# main.net
KiCad netlist of a schematic drawn in Altium Designer
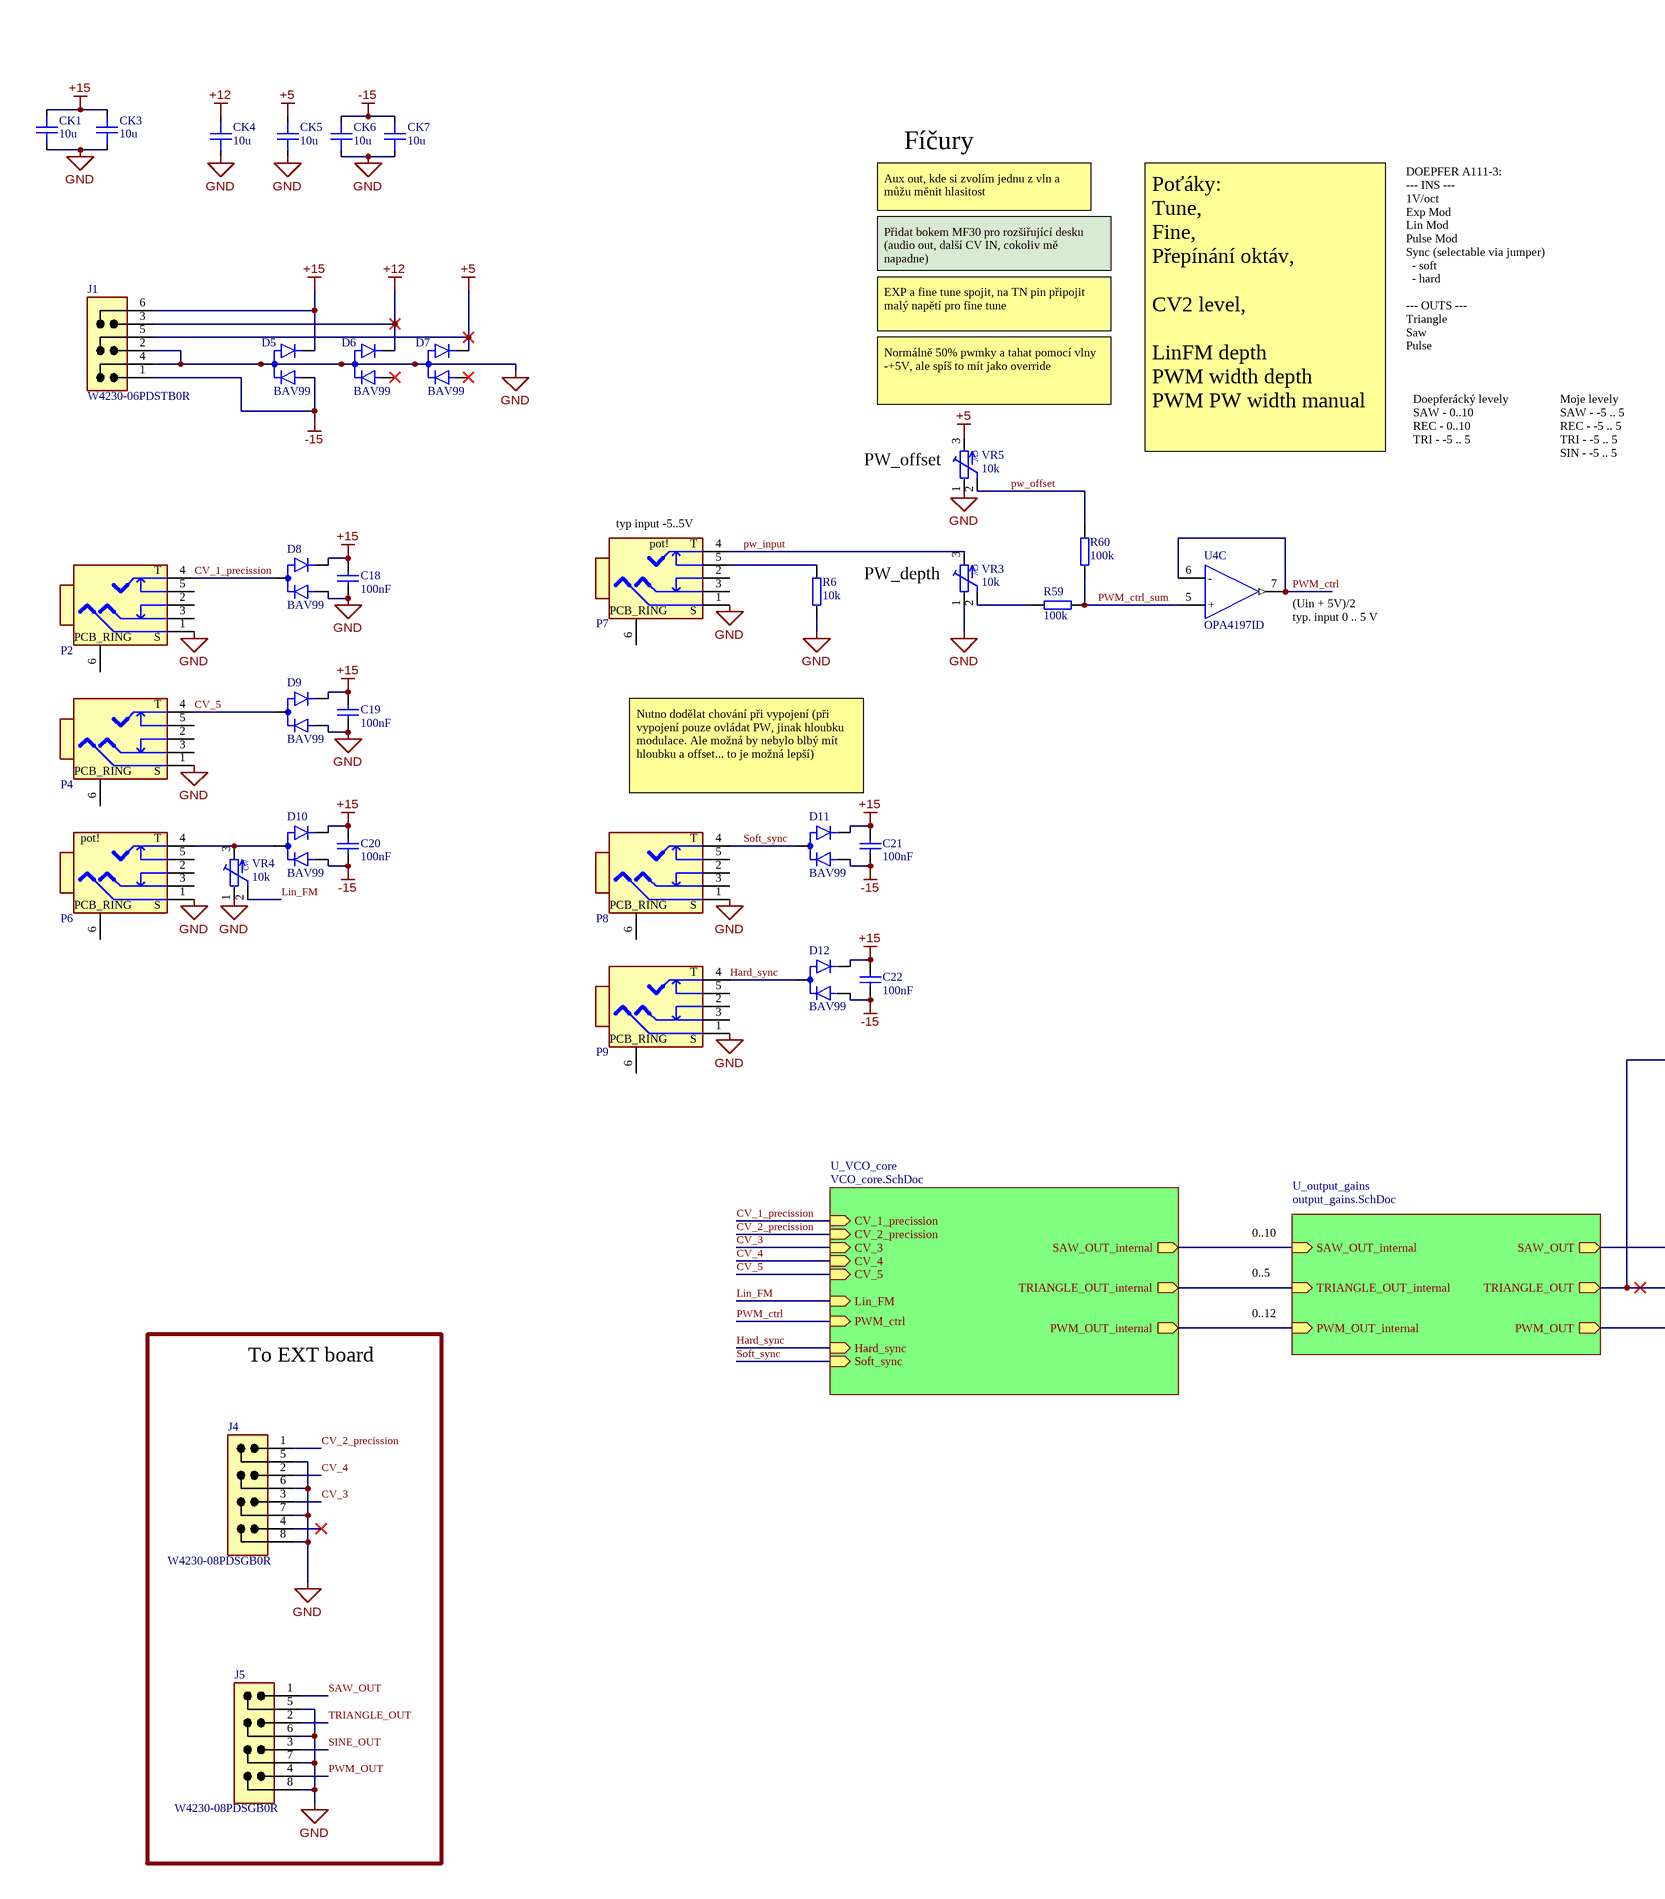
[diagram p0: main.SchDoc, left]
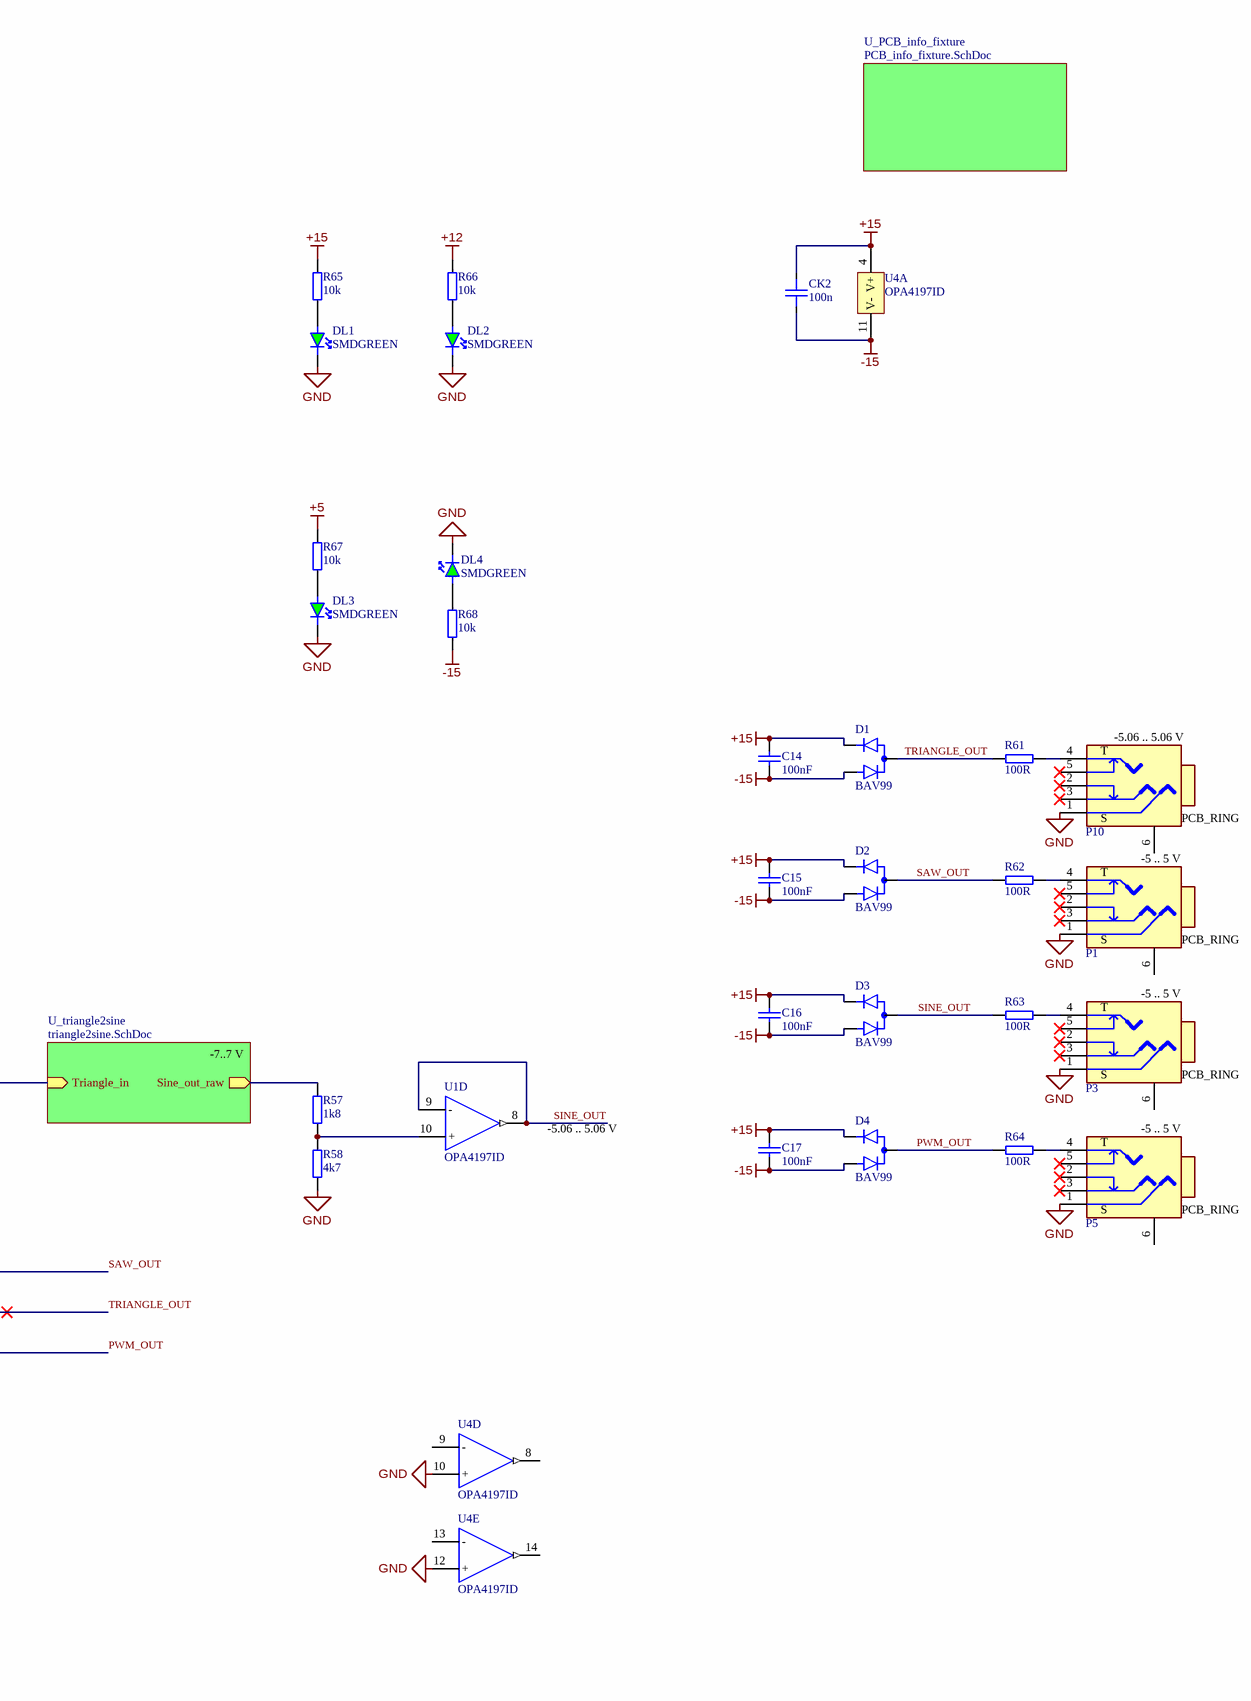
[diagram p1: main.SchDoc, right]

(export (version "E")
  (design (tool "Eeschema 10.0.6"))
  (components
    (comp (ref "C14")
      (value "100nF")
      (footprint "WCAP-CSGP_0603_L1.6W0.8H0.8_Reflow")
      (description "WCAP-CSGP Multilayer Ceramic Chip Capacitor, General Purpose, size 0603, X7R, 100nF, 50V")
      (fields
        (field (name "MANUFACTURER") "Wurth Elektronik")
        (field (name "MANUFACTURER PART NUMBER") "885012206095")
      )
      (libsource (lib "Altium_WCAP-CSGP (rev22a)") (part "885012206095"))
    )
    (comp (ref "C15")
      (value "100nF")
      (footprint "WCAP-CSGP_0603_L1.6W0.8H0.8_Reflow")
      (description "WCAP-CSGP Multilayer Ceramic Chip Capacitor, General Purpose, size 0603, X7R, 100nF, 50V")
      (fields
        (field (name "MANUFACTURER") "Wurth Elektronik")
        (field (name "MANUFACTURER PART NUMBER") "885012206095")
      )
      (libsource (lib "Altium_WCAP-CSGP (rev22a)") (part "885012206095"))
    )
    (comp (ref "C16")
      (value "100nF")
      (footprint "WCAP-CSGP_0603_L1.6W0.8H0.8_Reflow")
      (description "WCAP-CSGP Multilayer Ceramic Chip Capacitor, General Purpose, size 0603, X7R, 100nF, 50V")
      (fields
        (field (name "MANUFACTURER") "Wurth Elektronik")
        (field (name "MANUFACTURER PART NUMBER") "885012206095")
      )
      (libsource (lib "Altium_WCAP-CSGP (rev22a)") (part "885012206095"))
    )
    (comp (ref "C17")
      (value "100nF")
      (footprint "WCAP-CSGP_0603_L1.6W0.8H0.8_Reflow")
      (description "WCAP-CSGP Multilayer Ceramic Chip Capacitor, General Purpose, size 0603, X7R, 100nF, 50V")
      (fields
        (field (name "MANUFACTURER") "Wurth Elektronik")
        (field (name "MANUFACTURER PART NUMBER") "885012206095")
      )
      (libsource (lib "Altium_WCAP-CSGP (rev22a)") (part "885012206095"))
    )
    (comp (ref "C18")
      (value "100nF")
      (footprint "WCAP-CSGP_0603_L1.6W0.8H0.8_Reflow")
      (description "WCAP-CSGP Multilayer Ceramic Chip Capacitor, General Purpose, size 0603, X7R, 100nF, 50V")
      (fields
        (field (name "MANUFACTURER") "Wurth Elektronik")
        (field (name "MANUFACTURER PART NUMBER") "885012206095")
      )
      (libsource (lib "Altium_WCAP-CSGP (rev22a)") (part "885012206095"))
    )
    (comp (ref "C19")
      (value "100nF")
      (footprint "WCAP-CSGP_0603_L1.6W0.8H0.8_Reflow")
      (description "WCAP-CSGP Multilayer Ceramic Chip Capacitor, General Purpose, size 0603, X7R, 100nF, 50V")
      (fields
        (field (name "MANUFACTURER") "Wurth Elektronik")
        (field (name "MANUFACTURER PART NUMBER") "885012206095")
      )
      (libsource (lib "Altium_WCAP-CSGP (rev22a)") (part "885012206095"))
    )
    (comp (ref "C20")
      (value "100nF")
      (footprint "WCAP-CSGP_0603_L1.6W0.8H0.8_Reflow")
      (description "WCAP-CSGP Multilayer Ceramic Chip Capacitor, General Purpose, size 0603, X7R, 100nF, 50V")
      (fields
        (field (name "MANUFACTURER") "Wurth Elektronik")
        (field (name "MANUFACTURER PART NUMBER") "885012206095")
      )
      (libsource (lib "Altium_WCAP-CSGP (rev22a)") (part "885012206095"))
    )
    (comp (ref "C21")
      (value "100nF")
      (footprint "WCAP-CSGP_0603_L1.6W0.8H0.8_Reflow")
      (description "WCAP-CSGP Multilayer Ceramic Chip Capacitor, General Purpose, size 0603, X7R, 100nF, 50V")
      (fields
        (field (name "MANUFACTURER") "Wurth Elektronik")
        (field (name "MANUFACTURER PART NUMBER") "885012206095")
      )
      (libsource (lib "Altium_WCAP-CSGP (rev22a)") (part "885012206095"))
    )
    (comp (ref "C22")
      (value "100nF")
      (footprint "WCAP-CSGP_0603_L1.6W0.8H0.8_Reflow")
      (description "WCAP-CSGP Multilayer Ceramic Chip Capacitor, General Purpose, size 0603, X7R, 100nF, 50V")
      (fields
        (field (name "MANUFACTURER") "Wurth Elektronik")
        (field (name "MANUFACTURER PART NUMBER") "885012206095")
      )
      (libsource (lib "Altium_WCAP-CSGP (rev22a)") (part "885012206095"))
    )
    (comp (ref "CK1")
      (value "10u")
      (footprint "CAPC3225X27N(SMC1210)")
      (description "C; 10u; 50V; 10%; X7R; ??;")
      (fields
        (field (name "MANUFACTURER") "Murata: GRM32ER71H106KA12L;;Samsung Electro-mechanics: CL32B106KBJNNNE")
      )
      (libsource (lib "altium_sql") (part "CK"))
    )
    (comp (ref "CK2")
      (value "100n")
      (footprint "CAPC1608X09N(SMC0603)")
      (description "C; 100n; 50V; 10%; X7R; ??;")
      (libsource (lib "altium_sql") (part "CK"))
    )
    (comp (ref "CK3")
      (value "10u")
      (footprint "CAPC3225X27N(SMC1210)")
      (description "C; 10u; 50V; 10%; X7R; ??;")
      (fields
        (field (name "MANUFACTURER") "Murata: GRM32ER71H106KA12L;;Samsung Electro-mechanics: CL32B106KBJNNNE")
      )
      (libsource (lib "altium_sql") (part "CK"))
    )
    (comp (ref "CK4")
      (value "10u")
      (footprint "CAPC3225X27N(SMC1210)")
      (description "C; 10u; 50V; 10%; X7R; ??;")
      (fields
        (field (name "MANUFACTURER") "Murata: GRM32ER71H106KA12L;;Samsung Electro-mechanics: CL32B106KBJNNNE")
      )
      (libsource (lib "altium_sql") (part "CK"))
    )
    (comp (ref "CK5")
      (value "10u")
      (footprint "CAPC3225X27N(SMC1210)")
      (description "C; 10u; 50V; 10%; X7R; ??;")
      (fields
        (field (name "MANUFACTURER") "Murata: GRM32ER71H106KA12L;;Samsung Electro-mechanics: CL32B106KBJNNNE")
      )
      (libsource (lib "altium_sql") (part "CK"))
    )
    (comp (ref "CK6")
      (value "10u")
      (footprint "CAPC3225X27N(SMC1210)")
      (description "C; 10u; 50V; 10%; X7R; ??;")
      (fields
        (field (name "MANUFACTURER") "Murata: GRM32ER71H106KA12L;;Samsung Electro-mechanics: CL32B106KBJNNNE")
      )
      (libsource (lib "altium_sql") (part "CK"))
    )
    (comp (ref "CK7")
      (value "10u")
      (footprint "CAPC3225X27N(SMC1210)")
      (description "C; 10u; 50V; 10%; X7R; ??;")
      (fields
        (field (name "MANUFACTURER") "Murata: GRM32ER71H106KA12L;;Samsung Electro-mechanics: CL32B106KBJNNNE")
      )
      (libsource (lib "altium_sql") (part "CK"))
    )
    (comp (ref "D1")
      (value "BAV99")
      (footprint "SOT95P230X110-3N(SOT23)")
      (libsource (lib "Kubikova integrovana knihovna ") (part "BAV99"))
    )
    (comp (ref "D2")
      (value "BAV99")
      (footprint "SOT95P230X110-3N(SOT23)")
      (libsource (lib "Kubikova integrovana knihovna ") (part "BAV99"))
    )
    (comp (ref "D3")
      (value "BAV99")
      (footprint "SOT95P230X110-3N(SOT23)")
      (libsource (lib "Kubikova integrovana knihovna ") (part "BAV99"))
    )
    (comp (ref "D4")
      (value "BAV99")
      (footprint "SOT95P230X110-3N(SOT23)")
      (libsource (lib "Kubikova integrovana knihovna ") (part "BAV99"))
    )
    (comp (ref "D5")
      (value "BAV99")
      (footprint "SOT95P230X110-3N(SOT23)")
      (libsource (lib "Kubikova integrovana knihovna ") (part "BAV99"))
    )
    (comp (ref "D6")
      (value "BAV99")
      (footprint "SOT95P230X110-3N(SOT23)")
      (libsource (lib "Kubikova integrovana knihovna ") (part "BAV99"))
    )
    (comp (ref "D7")
      (value "BAV99")
      (footprint "SOT95P230X110-3N(SOT23)")
      (libsource (lib "Kubikova integrovana knihovna ") (part "BAV99"))
    )
    (comp (ref "D8")
      (value "BAV99")
      (footprint "SOT95P230X110-3N(SOT23)")
      (libsource (lib "Kubikova integrovana knihovna ") (part "BAV99"))
    )
    (comp (ref "D9")
      (value "BAV99")
      (footprint "SOT95P230X110-3N(SOT23)")
      (libsource (lib "Kubikova integrovana knihovna ") (part "BAV99"))
    )
    (comp (ref "D10")
      (value "BAV99")
      (footprint "SOT95P230X110-3N(SOT23)")
      (libsource (lib "Kubikova integrovana knihovna ") (part "BAV99"))
    )
    (comp (ref "D11")
      (value "BAV99")
      (footprint "SOT95P230X110-3N(SOT23)")
      (libsource (lib "Kubikova integrovana knihovna ") (part "BAV99"))
    )
    (comp (ref "D12")
      (value "BAV99")
      (footprint "SOT95P230X110-3N(SOT23)")
      (libsource (lib "Kubikova integrovana knihovna ") (part "BAV99"))
    )
    (comp (ref "DL1")
      (value "SMDGREEN")
      (footprint "DIOC2012X12N(SMLED0805)G")
      (description "Ind; Light; Green;")
      (fields (field (name "MANUFACTURER") "KINGBRIGHT: KP-2012MGC"))
      (libsource (lib "altium_sql") (part "DL_G"))
    )
    (comp (ref "DL2")
      (value "SMDGREEN")
      (footprint "DIOC2012X12N(SMLED0805)G")
      (description "Ind; Light; Green;")
      (fields (field (name "MANUFACTURER") "KINGBRIGHT: KP-2012MGC"))
      (libsource (lib "altium_sql") (part "DL_G"))
    )
    (comp (ref "DL3")
      (value "SMDGREEN")
      (footprint "DIOC2012X12N(SMLED0805)G")
      (description "Ind; Light; Green;")
      (fields (field (name "MANUFACTURER") "KINGBRIGHT: KP-2012MGC"))
      (libsource (lib "altium_sql") (part "DL_G"))
    )
    (comp (ref "DL4")
      (value "SMDGREEN")
      (footprint "DIOC2012X12N(SMLED0805)G")
      (description "Ind; Light; Green;")
      (fields (field (name "MANUFACTURER") "KINGBRIGHT: KP-2012MGC"))
      (libsource (lib "altium_sql") (part "DL_G"))
    )
    (comp (ref "J1")
      (value "W4230-06PDSTB0R")
      (footprint "W4230-06PDS")
      (description "Con; Micro Fit 3.0; 6x; PCB; Straight; 250V; 5A; Male; Tin; ??;")
      (fields
        (field (name "MANUFACTURER") "HSUAN MAO: W4230-06PDSTB0R;;HSUAN MAO: W4230-06PDSTB0N;;HSM: W4230-06PDSTB0R;;HSM: W4230-06PDSTB0N")
      )
      (libsource (lib "altium_sql") (part "EJ_2X3PIN_L_MALE"))
    )
    (comp (ref "J4")
      (value "W4230-08PDSGB0R")
      (footprint "W4230-08PDS")
      (description "Con; Micro Fit 3.0; 8x; PCB; Straight; 250V; 5A; Male; Gold; ??;")
      (libsource (lib "altium_sql") (part "EJ_2X4PIN_L_MALE"))
    )
    (comp (ref "J5")
      (value "W4230-08PDSGB0R")
      (footprint "W4230-08PDS")
      (description "Con; Micro Fit 3.0; 8x; PCB; Straight; 250V; 5A; Male; Gold; ??;")
      (libsource (lib "altium_sql") (part "EJ_2X4PIN_L_MALE"))
    )
    (comp (ref "P1")
      (value "NYS232")
      (footprint "NYS232")
      (description "6.3 mm jack, right angle, THT")
      (libsource (lib "") (part "NYS232_1"))
    )
    (comp (ref "P2")
      (value "NYS232")
      (footprint "NYS232")
      (description "6.3 mm jack, right angle, THT")
      (libsource (lib "Kubikova integrovana knihovna ") (part "NYS232"))
    )
    (comp (ref "P3")
      (value "NYS232")
      (footprint "NYS232")
      (description "6.3 mm jack, right angle, THT")
      (libsource (lib "") (part "NYS232_1"))
    )
    (comp (ref "P4")
      (value "NYS232")
      (footprint "NYS232")
      (description "6.3 mm jack, right angle, THT")
      (libsource (lib "Kubikova integrovana knihovna ") (part "NYS232"))
    )
    (comp (ref "P5")
      (value "NYS232")
      (footprint "NYS232")
      (description "6.3 mm jack, right angle, THT")
      (libsource (lib "") (part "NYS232_1"))
    )
    (comp (ref "P6")
      (value "NYS232")
      (footprint "NYS232")
      (description "6.3 mm jack, right angle, THT")
      (libsource (lib "Kubikova integrovana knihovna ") (part "NYS232"))
    )
    (comp (ref "P7")
      (value "NYS232")
      (footprint "NYS232")
      (description "6.3 mm jack, right angle, THT")
      (libsource (lib "Kubikova integrovana knihovna ") (part "NYS232"))
    )
    (comp (ref "P8")
      (value "NYS232")
      (footprint "NYS232")
      (description "6.3 mm jack, right angle, THT")
      (libsource (lib "Kubikova integrovana knihovna ") (part "NYS232"))
    )
    (comp (ref "P9")
      (value "NYS232")
      (footprint "NYS232")
      (description "6.3 mm jack, right angle, THT")
      (libsource (lib "Kubikova integrovana knihovna ") (part "NYS232"))
    )
    (comp (ref "P10")
      (value "NYS232")
      (footprint "NYS232")
      (description "6.3 mm jack, right angle, THT")
      (libsource (lib "") (part "NYS232_1"))
    )
    (comp (ref "R6")
      (value "10k")
      (footprint "RESC1608X06N(SMR0603)")
      (description "Thick Film resistor, 0603 Size, universal value, 0.1 W")
      (libsource (lib "Kubikova integrovana knihovna ") (part "R 0603 universal"))
    )
    (comp (ref "R57")
      (value "1k8")
      (footprint "RESC1608X06N(SMR0603)")
      (description "Thick Film resistor, 0603 Size, universal value, 0.1 W")
      (libsource (lib "Kubikova integrovana knihovna ") (part "R 0603 universal"))
    )
    (comp (ref "R58")
      (value "4k7")
      (footprint "RESC1608X06N(SMR0603)")
      (description "Thick Film resistor, 0603 Size, universal value, 0.1 W")
      (libsource (lib "Kubikova integrovana knihovna ") (part "R 0603 universal"))
    )
    (comp (ref "R59")
      (value "100k")
      (footprint "RESC1608X06N(SMR0603)")
      (description "Thick Film resistor, 0603 Size, universal value, 0.1 W")
      (libsource (lib "Kubikova integrovana knihovna ") (part "R 0603 universal"))
    )
    (comp (ref "R60")
      (value "100k")
      (footprint "RESC1608X06N(SMR0603)")
      (description "Thick Film resistor, 0603 Size, universal value, 0.1 W")
      (libsource (lib "Kubikova integrovana knihovna ") (part "R 0603 universal"))
    )
    (comp (ref "R61")
      (value "100R")
      (footprint "RESC1608X06N(SMR0603)")
      (description "Thick Film resistor, 0603 Size, universal value, 0.1 W")
      (libsource (lib "Kubikova integrovana knihovna ") (part "R 0603 universal"))
    )
    (comp (ref "R62")
      (value "100R")
      (footprint "RESC1608X06N(SMR0603)")
      (description "Thick Film resistor, 0603 Size, universal value, 0.1 W")
      (libsource (lib "Kubikova integrovana knihovna ") (part "R 0603 universal"))
    )
    (comp (ref "R63")
      (value "100R")
      (footprint "RESC1608X06N(SMR0603)")
      (description "Thick Film resistor, 0603 Size, universal value, 0.1 W")
      (libsource (lib "Kubikova integrovana knihovna ") (part "R 0603 universal"))
    )
    (comp (ref "R64")
      (value "100R")
      (footprint "RESC1608X06N(SMR0603)")
      (description "Thick Film resistor, 0603 Size, universal value, 0.1 W")
      (libsource (lib "Kubikova integrovana knihovna ") (part "R 0603 universal"))
    )
    (comp (ref "R65")
      (value "10k")
      (footprint "RESC1608X06N(SMR0603)")
      (description "Thick Film resistor, 0603 Size, universal value, 0.1 W")
      (libsource (lib "Kubikova integrovana knihovna ") (part "R 0603 universal"))
    )
    (comp (ref "R66")
      (value "10k")
      (footprint "RESC1608X06N(SMR0603)")
      (description "Thick Film resistor, 0603 Size, universal value, 0.1 W")
      (libsource (lib "Kubikova integrovana knihovna ") (part "R 0603 universal"))
    )
    (comp (ref "R67")
      (value "10k")
      (footprint "RESC1608X06N(SMR0603)")
      (description "Thick Film resistor, 0603 Size, universal value, 0.1 W")
      (libsource (lib "Kubikova integrovana knihovna ") (part "R 0603 universal"))
    )
    (comp (ref "R68")
      (value "10k")
      (footprint "RESC1608X06N(SMR0603)")
      (description "Thick Film resistor, 0603 Size, universal value, 0.1 W")
      (libsource (lib "Kubikova integrovana knihovna ") (part "R 0603 universal"))
    )
    (comp (ref "U1")
      (value "OPA4197ID")
      (footprint "SOIC127P600X175-14N(SO-14)")
      (description "IC; Opamp; 4.5V; 36V; 4x;")
      (libsource (lib "altium_sql") (part "OP_AMP_QUAD_1"))
    )
    (comp (ref "U4")
      (value "OPA4197ID")
      (footprint "SOIC127P600X175-14N(SO-14)")
      (description "IC; Opamp; 4.5V; 36V; 4x;")
      (libsource (lib "altium_sql") (part "OP_AMP_QUAD_1"))
    )
    (comp (ref "VR3")
      (value "10k")
      (footprint "64W")
      (description "093 - 3/8\" Square (10 mm) Multi-Turn Cermet Trimmer")
      (libsource (lib "Kubikova integrovana knihovna ") (part "Trimmer universal 3/8 (10mm)"))
    )
    (comp (ref "VR4")
      (value "10k")
      (footprint "64W")
      (description "093 - 3/8\" Square (10 mm) Multi-Turn Cermet Trimmer")
      (libsource (lib "Kubikova integrovana knihovna ") (part "Trimmer universal 3/8 (10mm)"))
    )
    (comp (ref "VR5")
      (value "10k")
      (footprint "64W")
      (description "093 - 3/8\" Square (10 mm) Multi-Turn Cermet Trimmer")
      (libsource (lib "Kubikova integrovana knihovna ") (part "Trimmer universal 3/8 (10mm)"))
    )
  )
  (nets
    (net (code "1") (name "+5") (class "Default")
      (node (ref "CK5") (pin "1") (pinfunction "1_1") (pintype "passive"))
      (node (ref "D7") (pin "2") (pinfunction "C2_2") (pintype "passive"))
      (node (ref "J1") (pin "5") (pinfunction "5_5") (pintype "passive"))
      (node (ref "R67") (pin "2") (pinfunction "2_2") (pintype "passive"))
      (node (ref "VR5") (pin "3") (pinfunction "3_3") (pintype "passive"))
    )
    (net (code "2") (name "+12") (class "Default")
      (node (ref "CK4") (pin "1") (pinfunction "1_1") (pintype "passive"))
      (node (ref "D6") (pin "2") (pinfunction "C2_2") (pintype "passive"))
      (node (ref "J1") (pin "3") (pinfunction "3_3") (pintype "passive"))
      (node (ref "R66") (pin "2") (pinfunction "2_2") (pintype "passive"))
    )
    (net (code "3") (name "+15") (class "Default")
      (node (ref "C14") (pin "2") (pinfunction "2_2") (pintype "passive"))
      (node (ref "C15") (pin "2") (pinfunction "2_2") (pintype "passive"))
      (node (ref "C16") (pin "2") (pinfunction "2_2") (pintype "passive"))
      (node (ref "C17") (pin "2") (pinfunction "2_2") (pintype "passive"))
      (node (ref "C18") (pin "2") (pinfunction "2_2") (pintype "passive"))
      (node (ref "C19") (pin "2") (pinfunction "2_2") (pintype "passive"))
      (node (ref "C20") (pin "2") (pinfunction "2_2") (pintype "passive"))
      (node (ref "C21") (pin "2") (pinfunction "2_2") (pintype "passive"))
      (node (ref "C22") (pin "2") (pinfunction "2_2") (pintype "passive"))
      (node (ref "CK1") (pin "1") (pinfunction "1_1") (pintype "passive"))
      (node (ref "CK2") (pin "1") (pinfunction "1_1") (pintype "passive"))
      (node (ref "CK3") (pin "1") (pinfunction "1_1") (pintype "passive"))
      (node (ref "D1") (pin "2") (pinfunction "C2_2") (pintype "passive"))
      (node (ref "D10") (pin "2") (pinfunction "C2_2") (pintype "passive"))
      (node (ref "D11") (pin "2") (pinfunction "C2_2") (pintype "passive"))
      (node (ref "D12") (pin "2") (pinfunction "C2_2") (pintype "passive"))
      (node (ref "D2") (pin "2") (pinfunction "C2_2") (pintype "passive"))
      (node (ref "D3") (pin "2") (pinfunction "C2_2") (pintype "passive"))
      (node (ref "D4") (pin "2") (pinfunction "C2_2") (pintype "passive"))
      (node (ref "D5") (pin "2") (pinfunction "C2_2") (pintype "passive"))
      (node (ref "D8") (pin "2") (pinfunction "C2_2") (pintype "passive"))
      (node (ref "D9") (pin "2") (pinfunction "C2_2") (pintype "passive"))
      (node (ref "J1") (pin "6") (pinfunction "6_6") (pintype "passive"))
      (node (ref "R65") (pin "2") (pinfunction "2_2") (pintype "passive"))
      (node (ref "U4") (pin "4") (pinfunction "V+_4") (pintype "power_in"))
    )
    (net (code "4") (name "-15") (class "Default")
      (node (ref "C14") (pin "1") (pinfunction "1_1") (pintype "passive"))
      (node (ref "C15") (pin "1") (pinfunction "1_1") (pintype "passive"))
      (node (ref "C16") (pin "1") (pinfunction "1_1") (pintype "passive"))
      (node (ref "C17") (pin "1") (pinfunction "1_1") (pintype "passive"))
      (node (ref "C20") (pin "1") (pinfunction "1_1") (pintype "passive"))
      (node (ref "C21") (pin "1") (pinfunction "1_1") (pintype "passive"))
      (node (ref "C22") (pin "1") (pinfunction "1_1") (pintype "passive"))
      (node (ref "CK2") (pin "2") (pinfunction "2_2") (pintype "passive"))
      (node (ref "CK6") (pin "1") (pinfunction "1_1") (pintype "passive"))
      (node (ref "CK7") (pin "1") (pinfunction "1_1") (pintype "passive"))
      (node (ref "D1") (pin "1") (pinfunction "A1_1") (pintype "passive"))
      (node (ref "D10") (pin "1") (pinfunction "A1_1") (pintype "passive"))
      (node (ref "D11") (pin "1") (pinfunction "A1_1") (pintype "passive"))
      (node (ref "D12") (pin "1") (pinfunction "A1_1") (pintype "passive"))
      (node (ref "D2") (pin "1") (pinfunction "A1_1") (pintype "passive"))
      (node (ref "D3") (pin "1") (pinfunction "A1_1") (pintype "passive"))
      (node (ref "D4") (pin "1") (pinfunction "A1_1") (pintype "passive"))
      (node (ref "D5") (pin "1") (pinfunction "A1_1") (pintype "passive"))
      (node (ref "J1") (pin "1") (pinfunction "1_1") (pintype "passive"))
      (node (ref "R68") (pin "1") (pinfunction "1_1") (pintype "passive"))
      (node (ref "U4") (pin "11") (pinfunction "V-_11") (pintype "power_in"))
    )
    (net (code "5") (name "/CV_1_precission") (class "Default")
      (node (ref "D8") (pin "3") (pinfunction "C1A2_3") (pintype "passive"))
      (node (ref "P2") (pin "4") (pinfunction "TN_4") (pintype "passive"))
    )
    (net (code "6") (name "/CV_2_precission") (class "Default")
      (node (ref "J4") (pin "1") (pinfunction "1_1") (pintype "passive"))
    )
    (net (code "7") (name "/CV_3") (class "Default")
      (node (ref "J4") (pin "3") (pinfunction "3_3") (pintype "passive"))
    )
    (net (code "8") (name "/CV_4") (class "Default")
      (node (ref "J4") (pin "2") (pinfunction "2_2") (pintype "passive"))
    )
    (net (code "9") (name "/CV_5") (class "Default")
      (node (ref "D9") (pin "3") (pinfunction "C1A2_3") (pintype "passive"))
      (node (ref "P4") (pin "4") (pinfunction "TN_4") (pintype "passive"))
    )
    (net (code "10") (name "/Hard_sync") (class "Default")
      (node (ref "D12") (pin "3") (pinfunction "C1A2_3") (pintype "passive"))
      (node (ref "P9") (pin "4") (pinfunction "TN_4") (pintype "passive"))
    )
    (net (code "11") (name "/Lin_FM") (class "Default")
      (node (ref "VR4") (pin "2") (pinfunction "2_2") (pintype "passive"))
    )
    (net (code "12") (name "/PWM_OUT") (class "Default")
      (node (ref "D4") (pin "3") (pinfunction "C1A2_3") (pintype "passive"))
      (node (ref "J5") (pin "4") (pinfunction "4_4") (pintype "passive"))
      (node (ref "R64") (pin "1") (pinfunction "1_1") (pintype "passive"))
    )
    (net (code "14") (name "/PWM_ctrl") (class "Default")
      (node (ref "U4") (pin "6") (pinfunction "-_6") (pintype "passive"))
      (node (ref "U4") (pin "7") (pinfunction "OUT2_7") (pintype "output"))
    )
    (net (code "15") (name "/PWM_ctrl_sum") (class "Default")
      (node (ref "R59") (pin "1") (pinfunction "1_1") (pintype "passive"))
      (node (ref "R60") (pin "1") (pinfunction "1_1") (pintype "passive"))
      (node (ref "U4") (pin "5") (pinfunction "+_5") (pintype "passive"))
    )
    (net (code "16") (name "/SAW_OUT") (class "Default")
      (node (ref "D2") (pin "3") (pinfunction "C1A2_3") (pintype "passive"))
      (node (ref "J5") (pin "1") (pinfunction "1_1") (pintype "passive"))
      (node (ref "R62") (pin "1") (pinfunction "1_1") (pintype "passive"))
    )
    (net (code "18") (name "/SINE_OUT") (class "Default")
      (node (ref "D3") (pin "3") (pinfunction "C1A2_3") (pintype "passive"))
      (node (ref "J5") (pin "3") (pinfunction "3_3") (pintype "passive"))
      (node (ref "R63") (pin "1") (pinfunction "1_1") (pintype "passive"))
      (node (ref "U1") (pin "8") (pinfunction "OUT3_8") (pintype "output"))
      (node (ref "U1") (pin "9") (pinfunction "-_9") (pintype "passive"))
    )
    (net (code "19") (name "/Sine_out_raw") (class "Default")
      (node (ref "R57") (pin "2") (pinfunction "2_2") (pintype "passive"))
    )
    (net (code "20") (name "/Soft_sync") (class "Default")
      (node (ref "D11") (pin "3") (pinfunction "C1A2_3") (pintype "passive"))
      (node (ref "P8") (pin "4") (pinfunction "TN_4") (pintype "passive"))
    )
    (net (code "21") (name "/TRIANGLE_OUT") (class "Default")
      (node (ref "D1") (pin "3") (pinfunction "C1A2_3") (pintype "passive"))
      (node (ref "J5") (pin "2") (pinfunction "2_2") (pintype "passive"))
      (node (ref "R61") (pin "1") (pinfunction "1_1") (pintype "passive"))
    )
    (net (code "23") (name "/pw_input") (class "Default")
      (node (ref "P7") (pin "4") (pinfunction "TN_4") (pintype "passive"))
      (node (ref "VR3") (pin "3") (pinfunction "3_3") (pintype "passive"))
    )
    (net (code "24") (name "/pw_offset") (class "Default")
      (node (ref "R60") (pin "2") (pinfunction "2_2") (pintype "passive"))
      (node (ref "VR5") (pin "2") (pinfunction "2_2") (pintype "passive"))
    )
    (net (code "25") (name "GND") (class "Default")
      (node (ref "C18") (pin "1") (pinfunction "1_1") (pintype "passive"))
      (node (ref "C19") (pin "1") (pinfunction "1_1") (pintype "passive"))
      (node (ref "CK1") (pin "2") (pinfunction "2_2") (pintype "passive"))
      (node (ref "CK3") (pin "2") (pinfunction "2_2") (pintype "passive"))
      (node (ref "CK4") (pin "2") (pinfunction "2_2") (pintype "passive"))
      (node (ref "CK5") (pin "2") (pinfunction "2_2") (pintype "passive"))
      (node (ref "CK6") (pin "2") (pinfunction "2_2") (pintype "passive"))
      (node (ref "CK7") (pin "2") (pinfunction "2_2") (pintype "passive"))
      (node (ref "D5") (pin "3") (pinfunction "C1A2_3") (pintype "passive"))
      (node (ref "D6") (pin "3") (pinfunction "C1A2_3") (pintype "passive"))
      (node (ref "D7") (pin "3") (pinfunction "C1A2_3") (pintype "passive"))
      (node (ref "D8") (pin "1") (pinfunction "A1_1") (pintype "passive"))
      (node (ref "D9") (pin "1") (pinfunction "A1_1") (pintype "passive"))
      (node (ref "DL1") (pin "1") (pinfunction "C_1") (pintype "passive"))
      (node (ref "DL2") (pin "1") (pinfunction "C_1") (pintype "passive"))
      (node (ref "DL3") (pin "1") (pinfunction "C_1") (pintype "passive"))
      (node (ref "DL4") (pin "1") (pinfunction "C_1") (pintype "passive"))
      (node (ref "J1") (pin "2") (pinfunction "2_2") (pintype "passive"))
      (node (ref "J1") (pin "4") (pinfunction "4_4") (pintype "passive"))
      (node (ref "J4") (pin "5") (pinfunction "5_5") (pintype "passive"))
      (node (ref "J4") (pin "6") (pinfunction "6_6") (pintype "passive"))
      (node (ref "J4") (pin "7") (pinfunction "7_7") (pintype "passive"))
      (node (ref "J4") (pin "8") (pinfunction "8_8") (pintype "passive"))
      (node (ref "J5") (pin "5") (pinfunction "5_5") (pintype "passive"))
      (node (ref "J5") (pin "6") (pinfunction "6_6") (pintype "passive"))
      (node (ref "J5") (pin "7") (pinfunction "7_7") (pintype "passive"))
      (node (ref "J5") (pin "8") (pinfunction "8_8") (pintype "passive"))
      (node (ref "P1") (pin "1") (pinfunction "S_1") (pintype "passive"))
      (node (ref "P10") (pin "1") (pinfunction "S_1") (pintype "passive"))
      (node (ref "P2") (pin "1") (pinfunction "S_1") (pintype "passive"))
      (node (ref "P3") (pin "1") (pinfunction "S_1") (pintype "passive"))
      (node (ref "P4") (pin "1") (pinfunction "S_1") (pintype "passive"))
      (node (ref "P5") (pin "1") (pinfunction "S_1") (pintype "passive"))
      (node (ref "P6") (pin "1") (pinfunction "S_1") (pintype "passive"))
      (node (ref "P7") (pin "1") (pinfunction "S_1") (pintype "passive"))
      (node (ref "P8") (pin "1") (pinfunction "S_1") (pintype "passive"))
      (node (ref "P9") (pin "1") (pinfunction "S_1") (pintype "passive"))
      (node (ref "R58") (pin "1") (pinfunction "1_1") (pintype "passive"))
      (node (ref "R6") (pin "1") (pinfunction "1_1") (pintype "passive"))
      (node (ref "U4") (pin "10") (pinfunction "+_10") (pintype "passive"))
      (node (ref "U4") (pin "12") (pinfunction "+_12") (pintype "passive"))
      (node (ref "VR3") (pin "1") (pinfunction "1_1") (pintype "passive"))
      (node (ref "VR4") (pin "1") (pinfunction "1_1") (pintype "passive"))
      (node (ref "VR5") (pin "1") (pinfunction "1_1") (pintype "passive"))
    )
    (net (code "26") (name "Net-(D10-C1A2)") (class "Default")
      (node (ref "D10") (pin "3") (pinfunction "C1A2_3") (pintype "passive"))
      (node (ref "P6") (pin "4") (pinfunction "TN_4") (pintype "passive"))
      (node (ref "VR4") (pin "3") (pinfunction "3_3") (pintype "passive"))
    )
    (net (code "27") (name "Net-(DL1-A)") (class "Default")
      (node (ref "DL1") (pin "2") (pinfunction "A_2") (pintype "passive"))
      (node (ref "R65") (pin "1") (pinfunction "1_1") (pintype "passive"))
    )
    (net (code "28") (name "Net-(DL2-A)") (class "Default")
      (node (ref "DL2") (pin "2") (pinfunction "A_2") (pintype "passive"))
      (node (ref "R66") (pin "1") (pinfunction "1_1") (pintype "passive"))
    )
    (net (code "29") (name "Net-(DL3-A)") (class "Default")
      (node (ref "DL3") (pin "2") (pinfunction "A_2") (pintype "passive"))
      (node (ref "R67") (pin "1") (pinfunction "1_1") (pintype "passive"))
    )
    (net (code "30") (name "Net-(DL4-A)") (class "Default")
      (node (ref "DL4") (pin "2") (pinfunction "A_2") (pintype "passive"))
      (node (ref "R68") (pin "2") (pinfunction "2_2") (pintype "passive"))
    )
    (net (code "31") (name "Net-(P1-TN)") (class "Default")
      (node (ref "P1") (pin "4") (pinfunction "TN_4") (pintype "passive"))
      (node (ref "R62") (pin "2") (pinfunction "2_2") (pintype "passive"))
    )
    (net (code "32") (name "Net-(P3-TN)") (class "Default")
      (node (ref "P3") (pin "4") (pinfunction "TN_4") (pintype "passive"))
      (node (ref "R63") (pin "2") (pinfunction "2_2") (pintype "passive"))
    )
    (net (code "33") (name "Net-(P5-TN)") (class "Default")
      (node (ref "P5") (pin "4") (pinfunction "TN_4") (pintype "passive"))
      (node (ref "R64") (pin "2") (pinfunction "2_2") (pintype "passive"))
    )
    (net (code "34") (name "Net-(P7-T)") (class "Default")
      (node (ref "P7") (pin "5") (pinfunction "T_5") (pintype "passive"))
      (node (ref "R6") (pin "2") (pinfunction "2_2") (pintype "passive"))
    )
    (net (code "35") (name "Net-(P10-TN)") (class "Default")
      (node (ref "P10") (pin "4") (pinfunction "TN_4") (pintype "passive"))
      (node (ref "R61") (pin "2") (pinfunction "2_2") (pintype "passive"))
    )
    (net (code "36") (name "Net-(R59-Pad2)") (class "Default")
      (node (ref "R59") (pin "2") (pinfunction "2_2") (pintype "passive"))
      (node (ref "VR3") (pin "2") (pinfunction "2_2") (pintype "passive"))
    )
    (net (code "37") (name "Net-(U1D-+)") (class "Default")
      (node (ref "R57") (pin "1") (pinfunction "1_1") (pintype "passive"))
      (node (ref "R58") (pin "2") (pinfunction "2_2") (pintype "passive"))
      (node (ref "U1") (pin "10") (pinfunction "+_10") (pintype "passive"))
    )
    (net (code "38") (name "unconnected-(D6-A1-Pad1)") (class "Default")
      (node (ref "D6") (pin "1") (pinfunction "A1_1") (pintype "passive+no_connect"))
    )
    (net (code "39") (name "unconnected-(D7-A1-Pad1)") (class "Default")
      (node (ref "D7") (pin "1") (pinfunction "A1_1") (pintype "passive+no_connect"))
    )
    (net (code "40") (name "unconnected-(J4-Pad4)") (class "Default")
      (node (ref "J4") (pin "4") (pinfunction "4_4") (pintype "passive+no_connect"))
    )
    (net (code "41") (name "unconnected-(P1-PCB_RING-Pad6)") (class "Default")
      (node (ref "P1") (pin "6") (pinfunction "PCB_RING_6") (pintype "passive"))
    )
    (net (code "42") (name "unconnected-(P1-R-Pad3)") (class "Default")
      (node (ref "P1") (pin "3") (pinfunction "R_3") (pintype "passive+no_connect"))
    )
    (net (code "43") (name "unconnected-(P1-RN-Pad2)") (class "Default")
      (node (ref "P1") (pin "2") (pinfunction "RN_2") (pintype "passive+no_connect"))
    )
    (net (code "44") (name "unconnected-(P1-T-Pad5)") (class "Default")
      (node (ref "P1") (pin "5") (pinfunction "T_5") (pintype "passive+no_connect"))
    )
    (net (code "45") (name "unconnected-(P2-PCB_RING-Pad6)") (class "Default")
      (node (ref "P2") (pin "6") (pinfunction "PCB_RING_6") (pintype "passive"))
    )
    (net (code "46") (name "unconnected-(P2-R-Pad3)") (class "Default")
      (node (ref "P2") (pin "3") (pinfunction "R_3") (pintype "passive"))
    )
    (net (code "47") (name "unconnected-(P2-RN-Pad2)") (class "Default")
      (node (ref "P2") (pin "2") (pinfunction "RN_2") (pintype "passive"))
    )
    (net (code "48") (name "unconnected-(P2-T-Pad5)") (class "Default")
      (node (ref "P2") (pin "5") (pinfunction "T_5") (pintype "passive"))
    )
    (net (code "49") (name "unconnected-(P3-PCB_RING-Pad6)") (class "Default")
      (node (ref "P3") (pin "6") (pinfunction "PCB_RING_6") (pintype "passive"))
    )
    (net (code "50") (name "unconnected-(P3-R-Pad3)") (class "Default")
      (node (ref "P3") (pin "3") (pinfunction "R_3") (pintype "passive+no_connect"))
    )
    (net (code "51") (name "unconnected-(P3-RN-Pad2)") (class "Default")
      (node (ref "P3") (pin "2") (pinfunction "RN_2") (pintype "passive+no_connect"))
    )
    (net (code "52") (name "unconnected-(P3-T-Pad5)") (class "Default")
      (node (ref "P3") (pin "5") (pinfunction "T_5") (pintype "passive+no_connect"))
    )
    (net (code "53") (name "unconnected-(P4-PCB_RING-Pad6)") (class "Default")
      (node (ref "P4") (pin "6") (pinfunction "PCB_RING_6") (pintype "passive"))
    )
    (net (code "54") (name "unconnected-(P4-R-Pad3)") (class "Default")
      (node (ref "P4") (pin "3") (pinfunction "R_3") (pintype "passive"))
    )
    (net (code "55") (name "unconnected-(P4-RN-Pad2)") (class "Default")
      (node (ref "P4") (pin "2") (pinfunction "RN_2") (pintype "passive"))
    )
    (net (code "56") (name "unconnected-(P4-T-Pad5)") (class "Default")
      (node (ref "P4") (pin "5") (pinfunction "T_5") (pintype "passive"))
    )
    (net (code "57") (name "unconnected-(P5-PCB_RING-Pad6)") (class "Default")
      (node (ref "P5") (pin "6") (pinfunction "PCB_RING_6") (pintype "passive"))
    )
    (net (code "58") (name "unconnected-(P5-R-Pad3)") (class "Default")
      (node (ref "P5") (pin "3") (pinfunction "R_3") (pintype "passive+no_connect"))
    )
    (net (code "59") (name "unconnected-(P5-RN-Pad2)") (class "Default")
      (node (ref "P5") (pin "2") (pinfunction "RN_2") (pintype "passive+no_connect"))
    )
    (net (code "60") (name "unconnected-(P5-T-Pad5)") (class "Default")
      (node (ref "P5") (pin "5") (pinfunction "T_5") (pintype "passive+no_connect"))
    )
    (net (code "61") (name "unconnected-(P6-PCB_RING-Pad6)") (class "Default")
      (node (ref "P6") (pin "6") (pinfunction "PCB_RING_6") (pintype "passive"))
    )
    (net (code "62") (name "unconnected-(P6-R-Pad3)") (class "Default")
      (node (ref "P6") (pin "3") (pinfunction "R_3") (pintype "passive"))
    )
    (net (code "63") (name "unconnected-(P6-RN-Pad2)") (class "Default")
      (node (ref "P6") (pin "2") (pinfunction "RN_2") (pintype "passive"))
    )
    (net (code "64") (name "unconnected-(P6-T-Pad5)") (class "Default")
      (node (ref "P6") (pin "5") (pinfunction "T_5") (pintype "passive"))
    )
    (net (code "65") (name "unconnected-(P7-PCB_RING-Pad6)") (class "Default")
      (node (ref "P7") (pin "6") (pinfunction "PCB_RING_6") (pintype "passive"))
    )
    (net (code "66") (name "unconnected-(P7-R-Pad3)") (class "Default")
      (node (ref "P7") (pin "3") (pinfunction "R_3") (pintype "passive"))
    )
    (net (code "67") (name "unconnected-(P7-RN-Pad2)") (class "Default")
      (node (ref "P7") (pin "2") (pinfunction "RN_2") (pintype "passive"))
    )
    (net (code "68") (name "unconnected-(P8-PCB_RING-Pad6)") (class "Default")
      (node (ref "P8") (pin "6") (pinfunction "PCB_RING_6") (pintype "passive"))
    )
    (net (code "69") (name "unconnected-(P8-R-Pad3)") (class "Default")
      (node (ref "P8") (pin "3") (pinfunction "R_3") (pintype "passive"))
    )
    (net (code "70") (name "unconnected-(P8-RN-Pad2)") (class "Default")
      (node (ref "P8") (pin "2") (pinfunction "RN_2") (pintype "passive"))
    )
    (net (code "71") (name "unconnected-(P8-T-Pad5)") (class "Default")
      (node (ref "P8") (pin "5") (pinfunction "T_5") (pintype "passive"))
    )
    (net (code "72") (name "unconnected-(P9-PCB_RING-Pad6)") (class "Default")
      (node (ref "P9") (pin "6") (pinfunction "PCB_RING_6") (pintype "passive"))
    )
    (net (code "73") (name "unconnected-(P9-R-Pad3)") (class "Default")
      (node (ref "P9") (pin "3") (pinfunction "R_3") (pintype "passive"))
    )
    (net (code "74") (name "unconnected-(P9-RN-Pad2)") (class "Default")
      (node (ref "P9") (pin "2") (pinfunction "RN_2") (pintype "passive"))
    )
    (net (code "75") (name "unconnected-(P9-T-Pad5)") (class "Default")
      (node (ref "P9") (pin "5") (pinfunction "T_5") (pintype "passive"))
    )
    (net (code "76") (name "unconnected-(P10-PCB_RING-Pad6)") (class "Default")
      (node (ref "P10") (pin "6") (pinfunction "PCB_RING_6") (pintype "passive"))
    )
    (net (code "77") (name "unconnected-(P10-R-Pad3)") (class "Default")
      (node (ref "P10") (pin "3") (pinfunction "R_3") (pintype "passive+no_connect"))
    )
    (net (code "78") (name "unconnected-(P10-RN-Pad2)") (class "Default")
      (node (ref "P10") (pin "2") (pinfunction "RN_2") (pintype "passive+no_connect"))
    )
    (net (code "79") (name "unconnected-(P10-T-Pad5)") (class "Default")
      (node (ref "P10") (pin "5") (pinfunction "T_5") (pintype "passive+no_connect"))
    )
    (net (code "80") (name "unconnected-(U4D---Pad9)") (class "Default")
      (node (ref "U4") (pin "9") (pinfunction "-_9") (pintype "passive"))
    )
    (net (code "81") (name "unconnected-(U4D-OUT3-Pad8)") (class "Default")
      (node (ref "U4") (pin "8") (pinfunction "OUT3_8") (pintype "output"))
    )
    (net (code "82") (name "unconnected-(U4E---Pad13)") (class "Default")
      (node (ref "U4") (pin "13") (pinfunction "-_13") (pintype "passive"))
    )
    (net (code "83") (name "unconnected-(U4E-OUT4-Pad14)") (class "Default")
      (node (ref "U4") (pin "14") (pinfunction "OUT4_14") (pintype "output"))
    )
  )
)
